# adapter.net
KiCad netlist of a schematic drawn in EAGLE
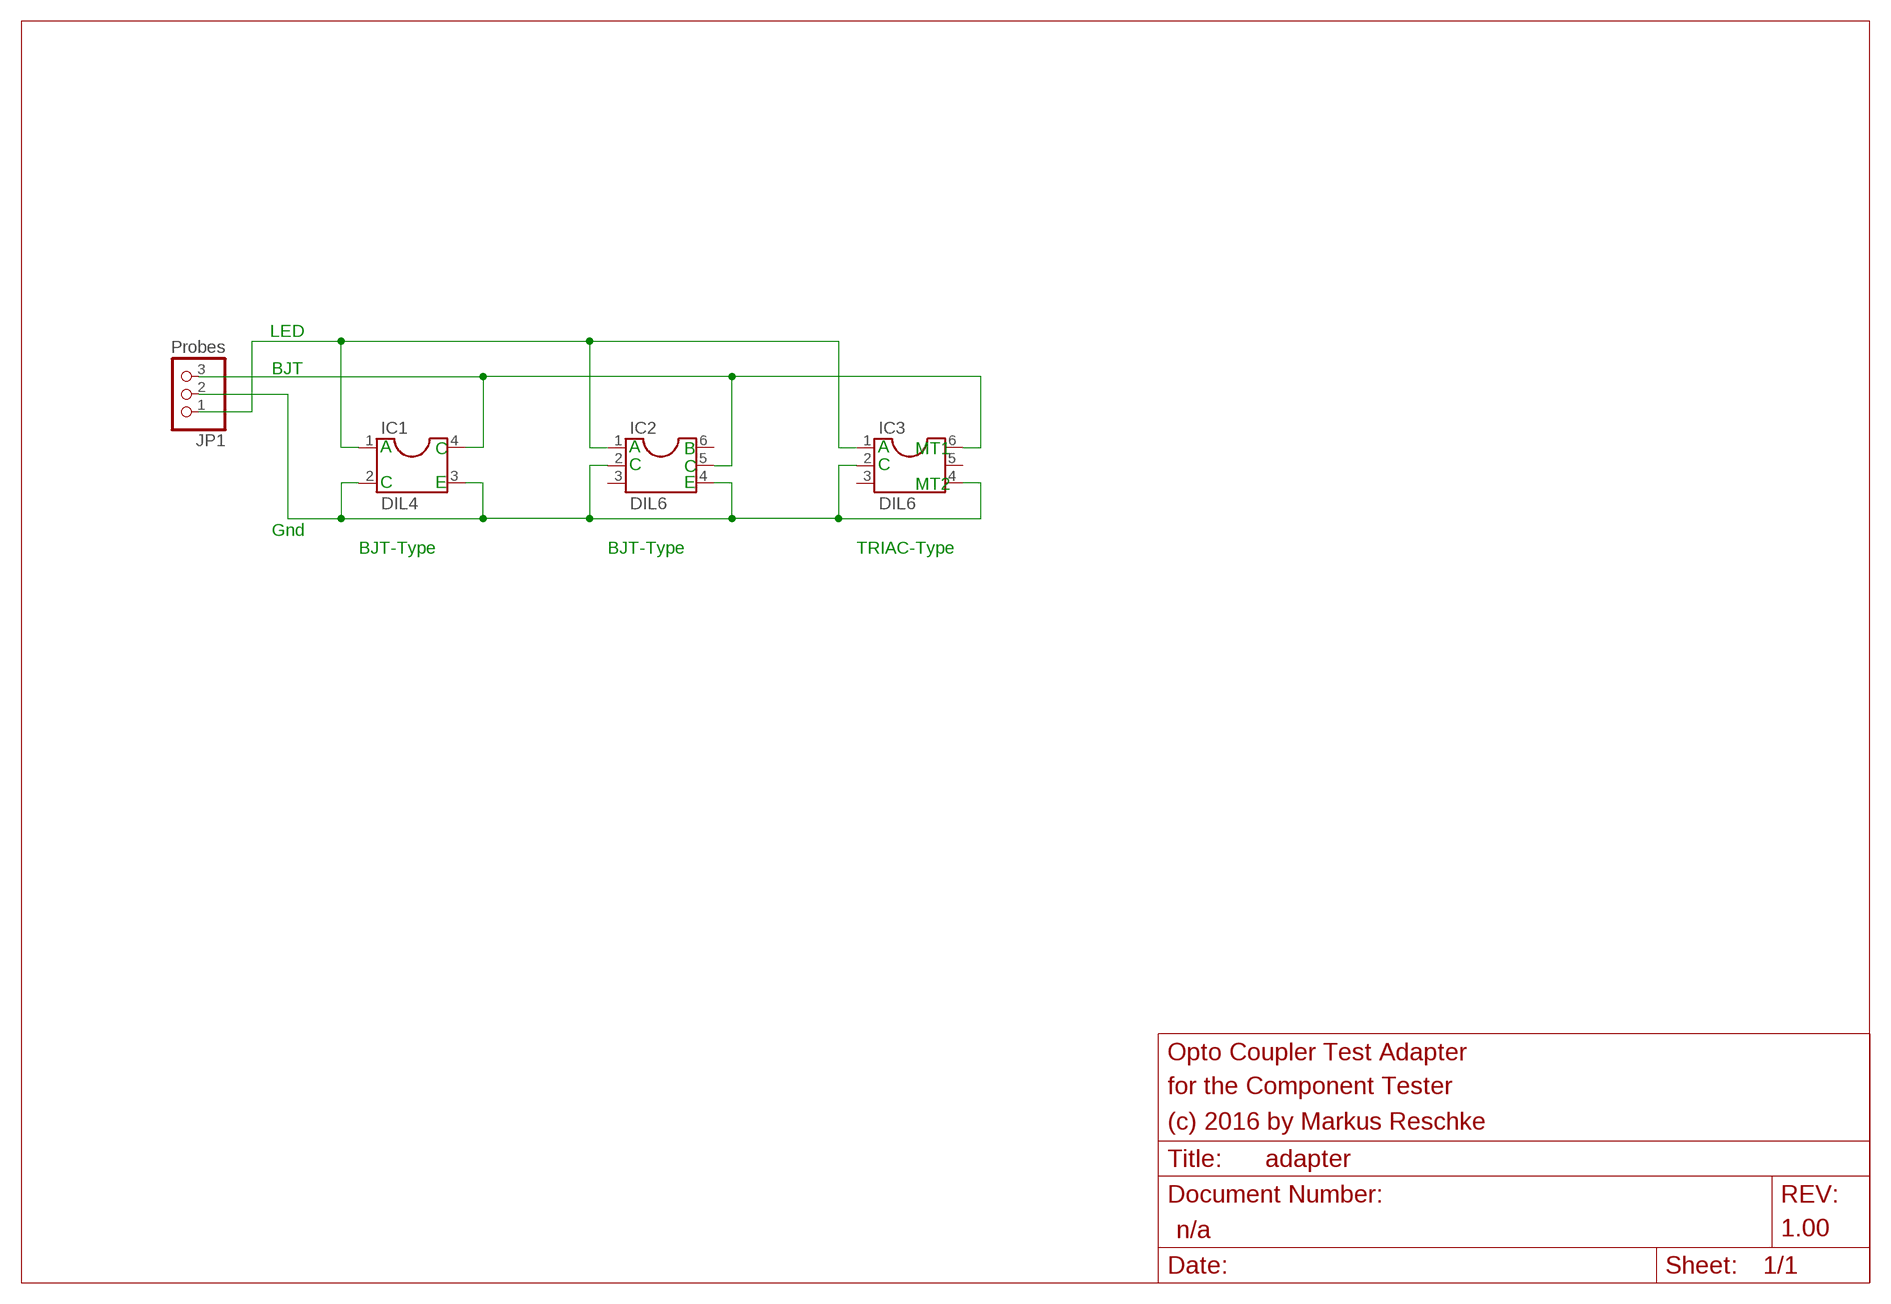
[diagram p0: schematic, sheet 1]

(export (version "E")
  (design (tool "Eeschema 10.0.6"))
  (components
    (comp (ref "IC1")
      (value "DIL4")
      (footprint "eagle-import:SOCKET-04")
      (libsource (lib "eagle-import") (part "DIL4S"))
    )
    (comp (ref "IC2")
      (value "DIL6")
      (footprint "eagle-import:SOCKET-06")
      (libsource (lib "eagle-import") (part "DIL6S"))
    )
    (comp (ref "IC3")
      (value "DIL6")
      (footprint "eagle-import:SOCKET-06")
      (libsource (lib "eagle-import") (part "DIL6S"))
    )
    (comp (ref "JP1")
      (value "Probes")
      (footprint "eagle-import:1X03_90")
      (libsource (lib "eagle-import") (part "PINHD-1X3/90"))
    )
  )
  (nets
    (net (code "1") (name "Net-(IC1-Pad1)") (class "Default")
      (node (ref "IC1") (pin "1") (pinfunction "1_1") (pintype "passive"))
      (node (ref "IC2") (pin "1") (pinfunction "1_1") (pintype "passive"))
      (node (ref "IC3") (pin "1") (pinfunction "1_1") (pintype "passive"))
      (node (ref "JP1") (pin "1") (pinfunction "1_1") (pintype "passive"))
    )
    (net (code "2") (name "Net-(IC1-Pad2)") (class "Default")
      (node (ref "IC1") (pin "2") (pinfunction "2_2") (pintype "passive"))
      (node (ref "IC1") (pin "3") (pinfunction "3_3") (pintype "passive"))
      (node (ref "IC2") (pin "2") (pinfunction "2_2") (pintype "passive"))
      (node (ref "IC2") (pin "4") (pinfunction "4_4") (pintype "passive"))
      (node (ref "IC3") (pin "2") (pinfunction "2_2") (pintype "passive"))
      (node (ref "IC3") (pin "4") (pinfunction "4_4") (pintype "passive"))
      (node (ref "JP1") (pin "2") (pinfunction "2_2") (pintype "passive"))
    )
    (net (code "3") (name "Net-(IC1-Pad4)") (class "Default")
      (node (ref "IC1") (pin "4") (pinfunction "4_4") (pintype "passive"))
      (node (ref "IC2") (pin "5") (pinfunction "5_5") (pintype "passive"))
      (node (ref "IC3") (pin "6") (pinfunction "6_6") (pintype "passive"))
      (node (ref "JP1") (pin "3") (pinfunction "3_3") (pintype "passive"))
    )
    (net (code "4") (name "unconnected-(IC2-Pad3)") (class "Default")
      (node (ref "IC2") (pin "3") (pinfunction "3_3") (pintype "passive"))
    )
    (net (code "5") (name "unconnected-(IC2-Pad6)") (class "Default")
      (node (ref "IC2") (pin "6") (pinfunction "6_6") (pintype "passive"))
    )
    (net (code "6") (name "unconnected-(IC3-Pad3)") (class "Default")
      (node (ref "IC3") (pin "3") (pinfunction "3_3") (pintype "passive"))
    )
    (net (code "7") (name "unconnected-(IC3-Pad5)") (class "Default")
      (node (ref "IC3") (pin "5") (pinfunction "5_5") (pintype "passive"))
    )
  )
)
